# peltier.net
KiCad netlist of a schematic drawn in EAGLE
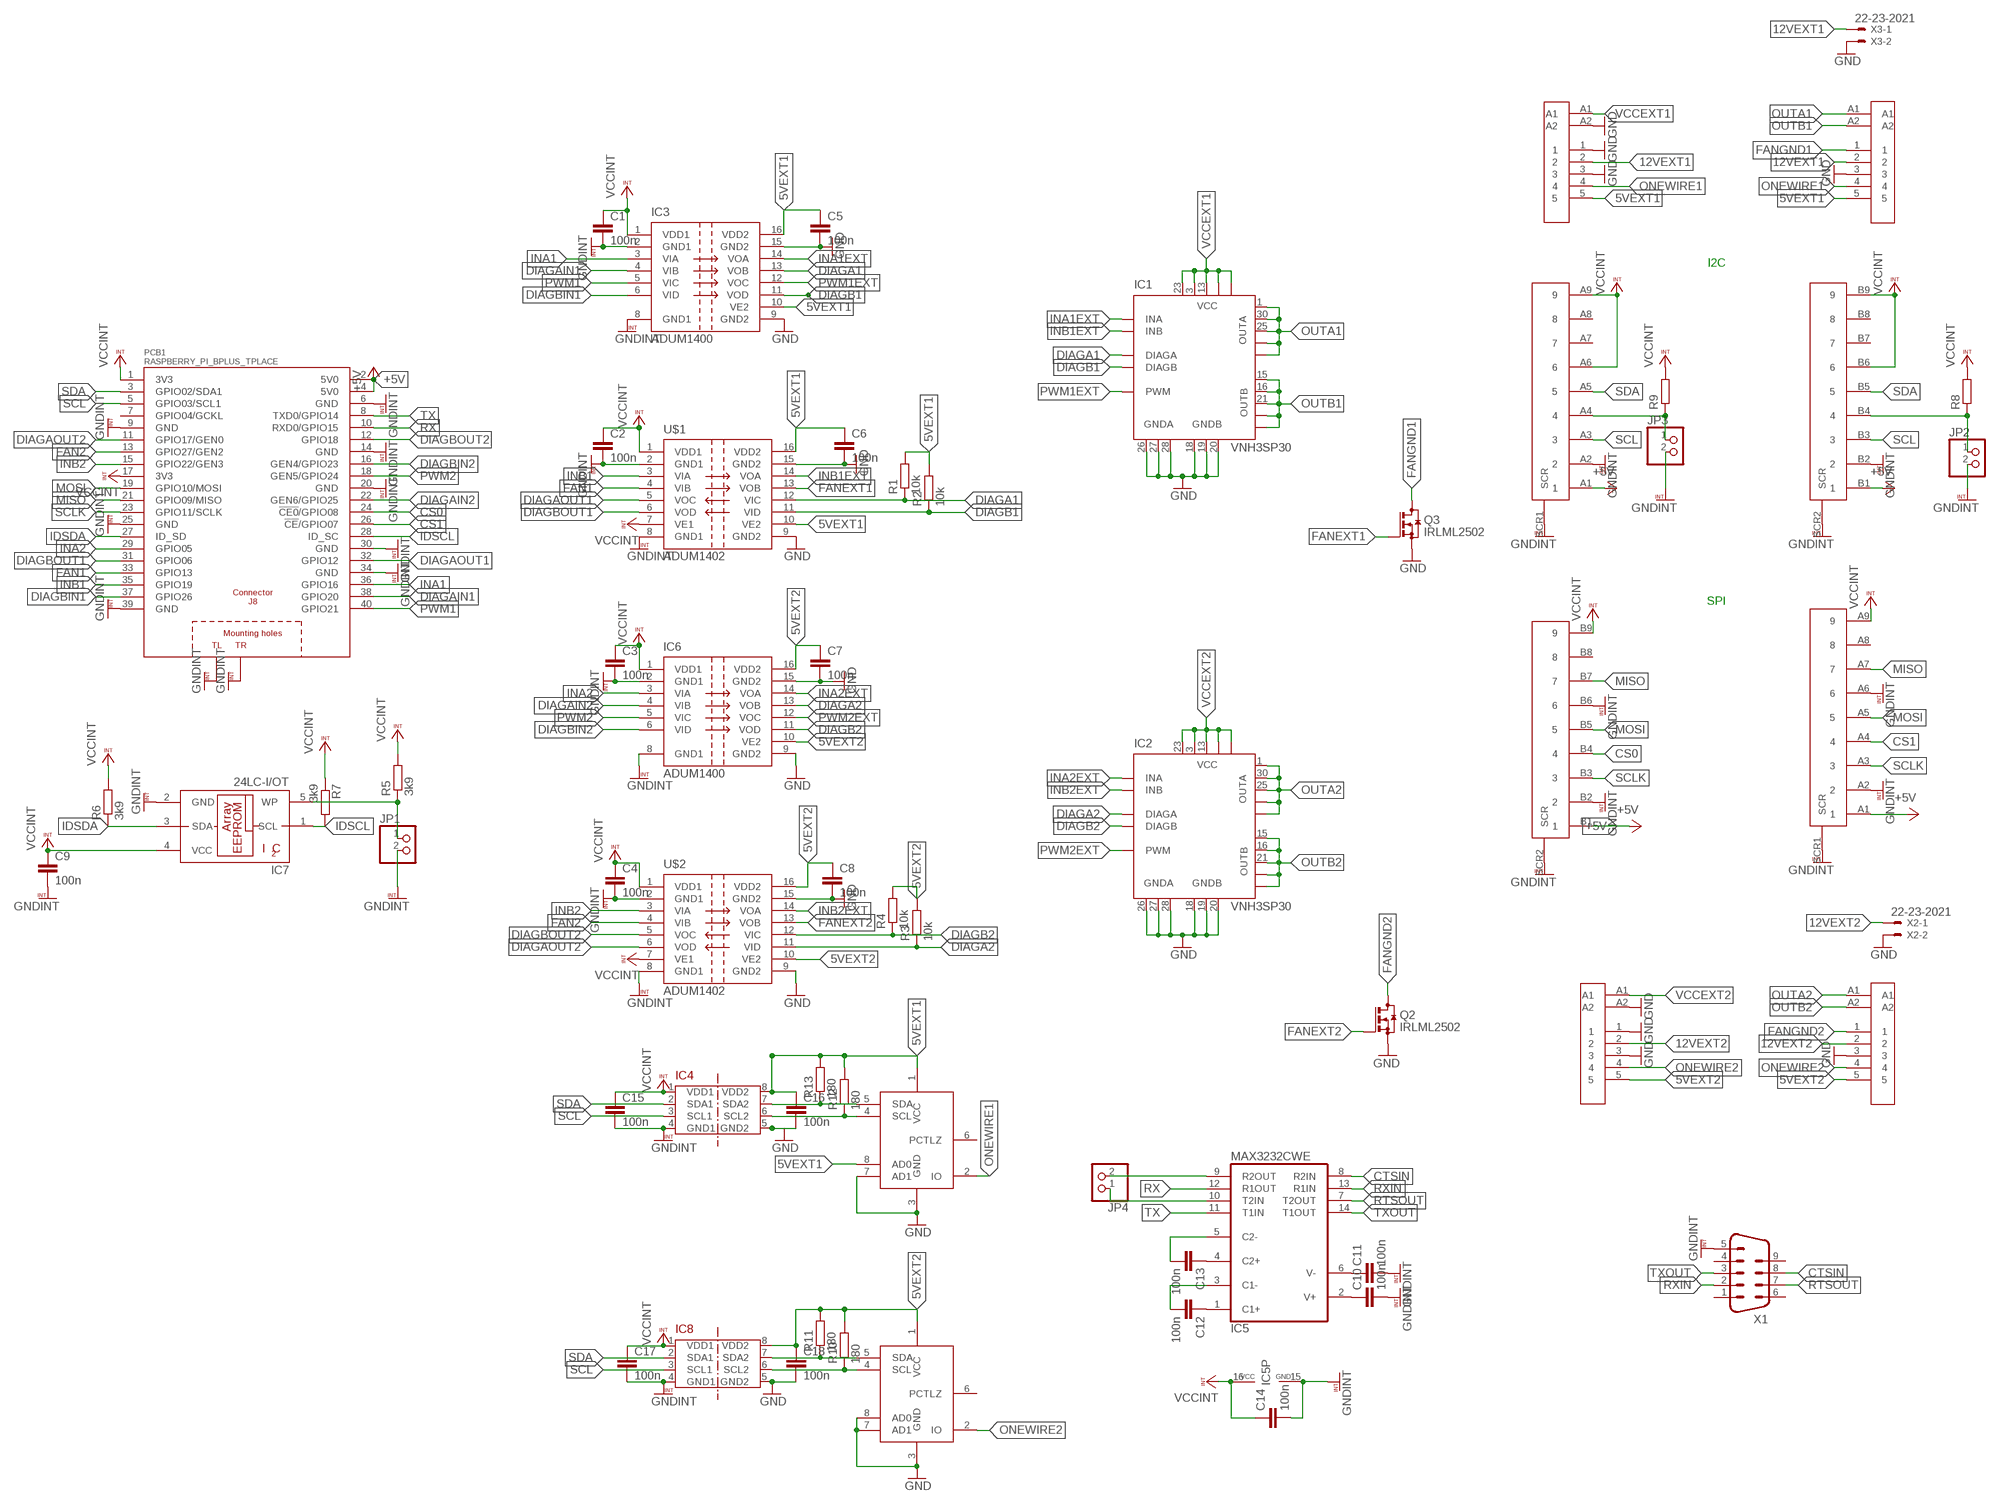
[diagram p0: schematic, sheet 1]

(export (version "E")
  (design (tool "Eeschema 10.0.6"))
  (components
    (comp (ref "C1")
      (value "100n")
      (footprint "eagle-import:C0805")
      (libsource (lib "eagle-import") (part "C-EUC0805"))
    )
    (comp (ref "C2")
      (value "100n")
      (footprint "eagle-import:C0805")
      (libsource (lib "eagle-import") (part "C-EUC0805"))
    )
    (comp (ref "C3")
      (value "100n")
      (footprint "eagle-import:C0805")
      (libsource (lib "eagle-import") (part "C-EUC0805"))
    )
    (comp (ref "C4")
      (value "100n")
      (footprint "eagle-import:C0805")
      (libsource (lib "eagle-import") (part "C-EUC0805"))
    )
    (comp (ref "C5")
      (value "100n")
      (footprint "eagle-import:C0805")
      (libsource (lib "eagle-import") (part "C-EUC0805"))
    )
    (comp (ref "C6")
      (value "100n")
      (footprint "eagle-import:C0805")
      (libsource (lib "eagle-import") (part "C-EUC0805"))
    )
    (comp (ref "C7")
      (value "100n")
      (footprint "eagle-import:C0805")
      (libsource (lib "eagle-import") (part "C-EUC0805"))
    )
    (comp (ref "C8")
      (value "100n")
      (footprint "eagle-import:C0805")
      (libsource (lib "eagle-import") (part "C-EUC0805"))
    )
    (comp (ref "C9")
      (value "100n")
      (footprint "eagle-import:C0805")
      (libsource (lib "eagle-import") (part "C-EUC0805"))
    )
    (comp (ref "C10")
      (value "100n")
      (footprint "eagle-import:C0805")
      (libsource (lib "eagle-import") (part "C-EUC0805"))
    )
    (comp (ref "C11")
      (value "100n")
      (footprint "eagle-import:C0805")
      (libsource (lib "eagle-import") (part "C-EUC0805"))
    )
    (comp (ref "C12")
      (value "100n")
      (footprint "eagle-import:C0805")
      (libsource (lib "eagle-import") (part "C-EUC0805"))
    )
    (comp (ref "C13")
      (value "100n")
      (footprint "eagle-import:C0805")
      (libsource (lib "eagle-import") (part "C-EUC0805"))
    )
    (comp (ref "C14")
      (value "100n")
      (footprint "eagle-import:C0805")
      (libsource (lib "eagle-import") (part "C-EUC0805"))
    )
    (comp (ref "C15")
      (value "100n")
      (footprint "eagle-import:C0805")
      (libsource (lib "eagle-import") (part "C-EUC0805"))
    )
    (comp (ref "C16")
      (value "100n")
      (footprint "eagle-import:C0805")
      (libsource (lib "eagle-import") (part "C-EUC0805"))
    )
    (comp (ref "C17")
      (value "100n")
      (footprint "eagle-import:C0805")
      (libsource (lib "eagle-import") (part "C-EUC0805"))
    )
    (comp (ref "C18")
      (value "100n")
      (footprint "eagle-import:C0805")
      (libsource (lib "eagle-import") (part "C-EUC0805"))
    )
    (comp (ref "IC1")
      (value "VNH3SP30")
      (footprint "eagle-import:MULTIPOWERSO-30")
      (fields (field (name "MPN") "VNH3SP30-E"))
      (libsource (lib "eagle-import") (part "VNH3SP30"))
    )
    (comp (ref "IC2")
      (value "VNH3SP30")
      (footprint "eagle-import:MULTIPOWERSO-30")
      (fields (field (name "MPN") "VNH3SP30-E"))
      (libsource (lib "eagle-import") (part "VNH3SP30"))
    )
    (comp (ref "IC3")
      (value "ADUM1400")
      (footprint "eagle-import:SO16W")
      (libsource (lib "eagle-import") (part "ADUM1400"))
    )
    (comp (ref "IC4")
      (value "ADUM1250")
      (footprint "eagle-import:SO08")
      (libsource (lib "eagle-import") (part "ADUM1250"))
    )
    (comp (ref "IC5")
      (value "MAX3232CWE")
      (footprint "eagle-import:SO16L")
      (fields (field (name "MF") "MAXIM") (field (name "MPN") "MAX3232CWE+"))
      (libsource (lib "eagle-import") (part "MAX3232WEC"))
    )
    (comp (ref "IC6")
      (value "ADUM1400")
      (footprint "eagle-import:SO16W")
      (libsource (lib "eagle-import") (part "ADUM1400"))
    )
    (comp (ref "IC7")
      (value "24LC-I/OT")
      (footprint "eagle-import:SOT23-5")
      (libsource (lib "eagle-import") (part "24LC-I/OT"))
    )
    (comp (ref "IC8")
      (value "ADUM1250")
      (footprint "eagle-import:SO08")
      (libsource (lib "eagle-import") (part "ADUM1250"))
    )
    (comp (ref "JP1")
      (value "PINHD-1X2")
      (footprint "eagle-import:1X02")
      (libsource (lib "eagle-import") (part "PINHD-1X2"))
    )
    (comp (ref "JP2")
      (value "PINHD-1X2")
      (footprint "eagle-import:1X02")
      (libsource (lib "eagle-import") (part "PINHD-1X2"))
    )
    (comp (ref "JP3")
      (value "PINHD-1X2")
      (footprint "eagle-import:1X02")
      (libsource (lib "eagle-import") (part "PINHD-1X2"))
    )
    (comp (ref "JP4")
      (value "PINHD-1X2")
      (footprint "eagle-import:1X02")
      (libsource (lib "eagle-import") (part "PINHD-1X2"))
    )
    (comp (ref "PCB1")
      (value "RASPBERRY_PI_BPLUS_TPLACE")
      (footprint "eagle-import:RASPBERRY_PI_BPLUS_TPLACE")
      (libsource (lib "eagle-import") (part "RASPBERRY_PI_BPLUS_TPLACE"))
    )
    (comp (ref "Q2")
      (value "IRLML2502")
      (footprint "eagle-import:SOT23")
      (libsource (lib "eagle-import") (part "BSS123"))
    )
    (comp (ref "Q3")
      (value "IRLML2502")
      (footprint "eagle-import:SOT23")
      (libsource (lib "eagle-import") (part "BSS123"))
    )
    (comp (ref "R1")
      (value "10k")
      (footprint "eagle-import:R0805")
      (libsource (lib "eagle-import") (part "R-EU_R0805"))
    )
    (comp (ref "R2")
      (value "10k")
      (footprint "eagle-import:R0805")
      (libsource (lib "eagle-import") (part "R-EU_R0805"))
    )
    (comp (ref "R3")
      (value "10k")
      (footprint "eagle-import:R0805")
      (libsource (lib "eagle-import") (part "R-EU_R0805"))
    )
    (comp (ref "R4")
      (value "10k")
      (footprint "eagle-import:R0805")
      (libsource (lib "eagle-import") (part "R-EU_R0805"))
    )
    (comp (ref "R5")
      (value "3k9")
      (footprint "eagle-import:R0805")
      (libsource (lib "eagle-import") (part "R-EU_R0805"))
    )
    (comp (ref "R6")
      (value "3k9")
      (footprint "eagle-import:R0805")
      (libsource (lib "eagle-import") (part "R-EU_R0805"))
    )
    (comp (ref "R7")
      (value "3k9")
      (footprint "eagle-import:R0805")
      (libsource (lib "eagle-import") (part "R-EU_R0805"))
    )
    (comp (ref "R8")
      (value "R-EU_R0805")
      (footprint "eagle-import:R0805")
      (libsource (lib "eagle-import") (part "R-EU_R0805"))
    )
    (comp (ref "R9")
      (value "R-EU_R0805")
      (footprint "eagle-import:R0805")
      (libsource (lib "eagle-import") (part "R-EU_R0805"))
    )
    (comp (ref "R10")
      (value "180")
      (footprint "eagle-import:R0805")
      (libsource (lib "eagle-import") (part "R-EU_R0805"))
    )
    (comp (ref "R11")
      (value "180")
      (footprint "eagle-import:R0805")
      (libsource (lib "eagle-import") (part "R-EU_R0805"))
    )
    (comp (ref "R12")
      (value "180")
      (footprint "eagle-import:R0805")
      (libsource (lib "eagle-import") (part "R-EU_R0805"))
    )
    (comp (ref "R13")
      (value "180")
      (footprint "eagle-import:R0805")
      (libsource (lib "eagle-import") (part "R-EU_R0805"))
    )
    (comp (ref "U$1")
      (value "ADUM1402")
      (footprint "eagle-import:SO16W")
      (libsource (lib "eagle-import") (part "ADUM1402"))
    )
    (comp (ref "U$2")
      (value "ADUM1402")
      (footprint "eagle-import:SO16W")
      (libsource (lib "eagle-import") (part "ADUM1402"))
    )
    (comp (ref "U$3")
      (value "7W2-F")
      (footprint "eagle-import:7W2-F")
      (libsource (lib "eagle-import") (part "7W2-F"))
    )
    (comp (ref "U$4")
      (value "7W2-F")
      (footprint "eagle-import:7W2-F")
      (libsource (lib "eagle-import") (part "7W2-F"))
    )
    (comp (ref "U$5")
      (value "7W2-M")
      (footprint "eagle-import:7W2-M")
      (libsource (lib "eagle-import") (part "7W2-M"))
    )
    (comp (ref "U$6")
      (value "7W2-M")
      (footprint "eagle-import:7W2-M")
      (libsource (lib "eagle-import") (part "7W2-M"))
    )
    (comp (ref "U$11")
      (value "164A19919X")
      (footprint "eagle-import:164A19919X")
      (libsource (lib "eagle-import") (part "164A19919X"))
    )
    (comp (ref "U$12")
      (value "164A19919X")
      (footprint "eagle-import:164A19919X")
      (libsource (lib "eagle-import") (part "164A19919X"))
    )
    (comp (ref "U$14")
      (value "DS2483-100")
      (footprint "eagle-import:SO-08")
      (libsource (lib "eagle-import") (part "DS2483-100"))
    )
    (comp (ref "U$15")
      (value "DS2483-100")
      (footprint "eagle-import:SO-08")
      (libsource (lib "eagle-import") (part "DS2483-100"))
    )
    (comp (ref "X1")
      (value "M09HP")
      (footprint "eagle-import:M09HP")
      (libsource (lib "eagle-import") (part "M09HP"))
    )
    (comp (ref "X2")
      (value "22-23-2021")
      (footprint "eagle-import:22-23-2021")
      (fields (field (name "MF") "MOLEX"))
      (libsource (lib "eagle-import") (part "22-23-2021"))
    )
    (comp (ref "X3")
      (value "22-23-2021")
      (footprint "eagle-import:22-23-2021")
      (fields (field (name "MF") "MOLEX"))
      (libsource (lib "eagle-import") (part "22-23-2021"))
    )
  )
  (nets
    (net (code "1") (name "+5V") (class "Default")
      (node (ref "PCB1") (pin "2") (pinfunction "5V0_2") (pintype "power_in"))
      (node (ref "PCB1") (pin "4") (pinfunction "5V0_4") (pintype "power_in"))
      (node (ref "U$11") (pin "A1") (pinfunction "1_A1") (pintype "bidirectional"))
      (node (ref "U$11") (pin "B1") (pinfunction "1_B1") (pintype "bidirectional"))
      (node (ref "U$12") (pin "A1") (pinfunction "1_A1") (pintype "bidirectional"))
      (node (ref "U$12") (pin "B1") (pinfunction "1_B1") (pintype "bidirectional"))
    )
    (net (code "2") (name "5VEXT1") (class "Default")
      (node (ref "C16") (pin "1") (pinfunction "1_1") (pintype "passive"))
      (node (ref "C5") (pin "1") (pinfunction "1_1") (pintype "passive"))
      (node (ref "C6") (pin "1") (pinfunction "1_1") (pintype "passive"))
      (node (ref "IC3") (pin "10") (pinfunction "VE2_10") (pintype "passive"))
      (node (ref "IC3") (pin "16") (pinfunction "VDD2_16") (pintype "power_in"))
      (node (ref "IC4") (pin "8") (pinfunction "VDD2_8") (pintype "power_in"))
      (node (ref "R1") (pin "2") (pinfunction "2_2") (pintype "passive"))
      (node (ref "R12") (pin "2") (pinfunction "2_2") (pintype "passive"))
      (node (ref "R13") (pin "2") (pinfunction "2_2") (pintype "passive"))
      (node (ref "R2") (pin "2") (pinfunction "2_2") (pintype "passive"))
      (node (ref "U$1") (pin "10") (pinfunction "VE2_10") (pintype "passive"))
      (node (ref "U$1") (pin "16") (pinfunction "VDD2_16") (pintype "power_in"))
      (node (ref "U$14") (pin "1") (pinfunction "VCC_1") (pintype "bidirectional"))
      (node (ref "U$14") (pin "8") (pinfunction "AD0_8") (pintype "bidirectional"))
      (node (ref "U$3") (pin "5") (pinfunction "5_5") (pintype "bidirectional"))
      (node (ref "U$5") (pin "5") (pinfunction "5_5") (pintype "bidirectional"))
    )
    (net (code "3") (name "5VEXT2") (class "Default")
      (node (ref "C18") (pin "1") (pinfunction "1_1") (pintype "passive"))
      (node (ref "C7") (pin "1") (pinfunction "1_1") (pintype "passive"))
      (node (ref "C8") (pin "1") (pinfunction "1_1") (pintype "passive"))
      (node (ref "IC6") (pin "10") (pinfunction "VE2_10") (pintype "passive"))
      (node (ref "IC6") (pin "16") (pinfunction "VDD2_16") (pintype "power_in"))
      (node (ref "IC8") (pin "8") (pinfunction "VDD2_8") (pintype "power_in"))
      (node (ref "R10") (pin "2") (pinfunction "2_2") (pintype "passive"))
      (node (ref "R11") (pin "2") (pinfunction "2_2") (pintype "passive"))
      (node (ref "R3") (pin "2") (pinfunction "2_2") (pintype "passive"))
      (node (ref "R4") (pin "2") (pinfunction "2_2") (pintype "passive"))
      (node (ref "U$15") (pin "1") (pinfunction "VCC_1") (pintype "bidirectional"))
      (node (ref "U$2") (pin "10") (pinfunction "VE2_10") (pintype "passive"))
      (node (ref "U$2") (pin "16") (pinfunction "VDD2_16") (pintype "power_in"))
      (node (ref "U$4") (pin "5") (pinfunction "5_5") (pintype "bidirectional"))
      (node (ref "U$6") (pin "5") (pinfunction "5_5") (pintype "bidirectional"))
    )
    (net (code "4") (name "12VEXT1") (class "Default")
      (node (ref "U$3") (pin "2") (pinfunction "2_2") (pintype "bidirectional"))
      (node (ref "U$5") (pin "2") (pinfunction "2_2") (pintype "bidirectional"))
      (node (ref "X3") (pin "1") (pinfunction "S_1") (pintype "passive"))
    )
    (net (code "5") (name "12VEXT2") (class "Default")
      (node (ref "U$4") (pin "2") (pinfunction "2_2") (pintype "bidirectional"))
      (node (ref "U$6") (pin "2") (pinfunction "2_2") (pintype "bidirectional"))
      (node (ref "X2") (pin "1") (pinfunction "S_1") (pintype "passive"))
    )
    (net (code "6") (name "CS0") (class "Default")
      (node (ref "PCB1") (pin "24") (pinfunction "~{CE0}/GPIO08_24") (pintype "bidirectional"))
      (node (ref "U$12") (pin "B4") (pinfunction "4_B4") (pintype "bidirectional"))
    )
    (net (code "7") (name "CS1") (class "Default")
      (node (ref "PCB1") (pin "26") (pinfunction "~{CE}/GPIO07_26") (pintype "bidirectional"))
      (node (ref "U$12") (pin "A4") (pinfunction "4_A4") (pintype "bidirectional"))
    )
    (net (code "8") (name "CTSIN") (class "Default")
      (node (ref "IC5") (pin "8") (pinfunction "R2IN_8") (pintype "input"))
      (node (ref "X1") (pin "8") (pinfunction "8_8") (pintype "passive"))
    )
    (net (code "9") (name "DIAGA1") (class "Default")
      (node (ref "IC1") (pin "6") (pinfunction "DIAGA_6") (pintype "open_collector"))
      (node (ref "IC3") (pin "13") (pinfunction "VOB_13") (pintype "output"))
      (node (ref "R1") (pin "1") (pinfunction "1_1") (pintype "passive"))
      (node (ref "U$1") (pin "12") (pinfunction "VIC_12") (pintype "input"))
    )
    (net (code "10") (name "DIAGA2") (class "Default")
      (node (ref "IC2") (pin "6") (pinfunction "DIAGA_6") (pintype "open_collector"))
      (node (ref "IC6") (pin "13") (pinfunction "VOB_13") (pintype "output"))
      (node (ref "R3") (pin "1") (pinfunction "1_1") (pintype "passive"))
      (node (ref "U$2") (pin "11") (pinfunction "VID_11") (pintype "input"))
    )
    (net (code "11") (name "DIAGAIN1") (class "Default")
      (node (ref "IC3") (pin "4") (pinfunction "VIB_4") (pintype "input"))
      (node (ref "PCB1") (pin "38") (pinfunction "GPIO20_38") (pintype "bidirectional"))
    )
    (net (code "12") (name "DIAGAIN2") (class "Default")
      (node (ref "IC6") (pin "4") (pinfunction "VIB_4") (pintype "input"))
      (node (ref "PCB1") (pin "22") (pinfunction "GEN6/GPIO25_22") (pintype "bidirectional"))
    )
    (net (code "13") (name "DIAGAOUT1") (class "Default")
      (node (ref "PCB1") (pin "32") (pinfunction "GPIO12_32") (pintype "bidirectional"))
      (node (ref "U$1") (pin "5") (pinfunction "VOC_5") (pintype "output"))
    )
    (net (code "14") (name "DIAGAOUT2") (class "Default")
      (node (ref "PCB1") (pin "11") (pinfunction "GPIO17/GEN0_11") (pintype "bidirectional"))
      (node (ref "U$2") (pin "6") (pinfunction "VOD_6") (pintype "output"))
    )
    (net (code "15") (name "DIAGB1") (class "Default")
      (node (ref "IC1") (pin "10") (pinfunction "DIAGB_10") (pintype "open_collector"))
      (node (ref "IC3") (pin "11") (pinfunction "VOD_11") (pintype "output"))
      (node (ref "R2") (pin "1") (pinfunction "1_1") (pintype "passive"))
      (node (ref "U$1") (pin "11") (pinfunction "VID_11") (pintype "input"))
    )
    (net (code "16") (name "DIAGB2") (class "Default")
      (node (ref "IC2") (pin "10") (pinfunction "DIAGB_10") (pintype "open_collector"))
      (node (ref "IC6") (pin "11") (pinfunction "VOD_11") (pintype "output"))
      (node (ref "R4") (pin "1") (pinfunction "1_1") (pintype "passive"))
      (node (ref "U$2") (pin "12") (pinfunction "VIC_12") (pintype "input"))
    )
    (net (code "17") (name "DIAGBIN1") (class "Default")
      (node (ref "IC3") (pin "6") (pinfunction "VID_6") (pintype "input"))
      (node (ref "PCB1") (pin "37") (pinfunction "GPIO26_37") (pintype "bidirectional"))
    )
    (net (code "18") (name "DIAGBIN2") (class "Default")
      (node (ref "IC6") (pin "6") (pinfunction "VID_6") (pintype "input"))
      (node (ref "PCB1") (pin "16") (pinfunction "GEN4/GPIO23_16") (pintype "bidirectional"))
    )
    (net (code "19") (name "DIAGBOUT1") (class "Default")
      (node (ref "PCB1") (pin "31") (pinfunction "GPIO06_31") (pintype "bidirectional"))
      (node (ref "U$1") (pin "6") (pinfunction "VOD_6") (pintype "output"))
    )
    (net (code "20") (name "DIAGBOUT2") (class "Default")
      (node (ref "PCB1") (pin "12") (pinfunction "GPIO18_12") (pintype "bidirectional"))
      (node (ref "U$2") (pin "5") (pinfunction "VOC_5") (pintype "output"))
    )
    (net (code "21") (name "FAN1") (class "Default")
      (node (ref "PCB1") (pin "33") (pinfunction "GPIO13_33") (pintype "bidirectional"))
      (node (ref "U$1") (pin "4") (pinfunction "VIB_4") (pintype "input"))
    )
    (net (code "22") (name "FAN2") (class "Default")
      (node (ref "PCB1") (pin "13") (pinfunction "GPIO27/GEN2_13") (pintype "bidirectional"))
      (node (ref "U$2") (pin "4") (pinfunction "VIB_4") (pintype "input"))
    )
    (net (code "23") (name "FANEXT1") (class "Default")
      (node (ref "Q3") (pin "1") (pinfunction "G_1") (pintype "passive"))
      (node (ref "U$1") (pin "13") (pinfunction "VOB_13") (pintype "output"))
    )
    (net (code "24") (name "FANEXT2") (class "Default")
      (node (ref "Q2") (pin "1") (pinfunction "G_1") (pintype "passive"))
      (node (ref "U$2") (pin "13") (pinfunction "VOB_13") (pintype "output"))
    )
    (net (code "25") (name "FANGND1") (class "Default")
      (node (ref "Q3") (pin "3") (pinfunction "D_3") (pintype "passive"))
      (node (ref "U$3") (pin "1") (pinfunction "1_1") (pintype "bidirectional"))
    )
    (net (code "26") (name "FANGND2") (class "Default")
      (node (ref "Q2") (pin "3") (pinfunction "D_3") (pintype "passive"))
      (node (ref "U$4") (pin "1") (pinfunction "1_1") (pintype "bidirectional"))
    )
    (net (code "27") (name "GND") (class "Default")
      (node (ref "C16") (pin "2") (pinfunction "2_2") (pintype "passive"))
      (node (ref "C18") (pin "2") (pinfunction "2_2") (pintype "passive"))
      (node (ref "C5") (pin "2") (pinfunction "2_2") (pintype "passive"))
      (node (ref "C6") (pin "2") (pinfunction "2_2") (pintype "passive"))
      (node (ref "C7") (pin "2") (pinfunction "2_2") (pintype "passive"))
      (node (ref "C8") (pin "2") (pinfunction "2_2") (pintype "passive"))
      (node (ref "IC1") (pin "18") (pinfunction "GNDB_18") (pintype "power_in"))
      (node (ref "IC1") (pin "19") (pinfunction "GNDB_19") (pintype "power_in"))
      (node (ref "IC1") (pin "20") (pinfunction "GNDB_20") (pintype "power_in"))
      (node (ref "IC1") (pin "26") (pinfunction "GNDA_26") (pintype "power_in"))
      (node (ref "IC1") (pin "27") (pinfunction "GNDA_27") (pintype "power_in"))
      (node (ref "IC1") (pin "28") (pinfunction "GNDA_28") (pintype "power_in"))
      (node (ref "IC2") (pin "18") (pinfunction "GNDB_18") (pintype "power_in"))
      (node (ref "IC2") (pin "19") (pinfunction "GNDB_19") (pintype "power_in"))
      (node (ref "IC2") (pin "20") (pinfunction "GNDB_20") (pintype "power_in"))
      (node (ref "IC2") (pin "26") (pinfunction "GNDA_26") (pintype "power_in"))
      (node (ref "IC2") (pin "27") (pinfunction "GNDA_27") (pintype "power_in"))
      (node (ref "IC2") (pin "28") (pinfunction "GNDA_28") (pintype "power_in"))
      (node (ref "IC3") (pin "15") (pinfunction "GND2_15") (pintype "power_in"))
      (node (ref "IC3") (pin "9") (pinfunction "GND2_9") (pintype "power_in"))
      (node (ref "IC4") (pin "5") (pinfunction "GND2_5") (pintype "power_in"))
      (node (ref "IC6") (pin "15") (pinfunction "GND2_15") (pintype "power_in"))
      (node (ref "IC6") (pin "9") (pinfunction "GND2_9") (pintype "power_in"))
      (node (ref "IC8") (pin "5") (pinfunction "GND2_5") (pintype "power_in"))
      (node (ref "Q2") (pin "2") (pinfunction "S_2") (pintype "passive"))
      (node (ref "Q3") (pin "2") (pinfunction "S_2") (pintype "passive"))
      (node (ref "U$1") (pin "15") (pinfunction "GND2_15") (pintype "power_in"))
      (node (ref "U$1") (pin "9") (pinfunction "GND2_9") (pintype "power_in"))
      (node (ref "U$14") (pin "3") (pinfunction "GND_3") (pintype "bidirectional"))
      (node (ref "U$14") (pin "7") (pinfunction "AD1_7") (pintype "bidirectional"))
      (node (ref "U$15") (pin "3") (pinfunction "GND_3") (pintype "bidirectional"))
      (node (ref "U$15") (pin "7") (pinfunction "AD1_7") (pintype "bidirectional"))
      (node (ref "U$15") (pin "8") (pinfunction "AD0_8") (pintype "bidirectional"))
      (node (ref "U$2") (pin "15") (pinfunction "GND2_15") (pintype "power_in"))
      (node (ref "U$2") (pin "9") (pinfunction "GND2_9") (pintype "power_in"))
      (node (ref "U$3") (pin "3") (pinfunction "3_3") (pintype "bidirectional"))
      (node (ref "U$4") (pin "3") (pinfunction "3_3") (pintype "bidirectional"))
      (node (ref "U$5") (pin "1") (pinfunction "1_1") (pintype "bidirectional"))
      (node (ref "U$5") (pin "3") (pinfunction "3_3") (pintype "bidirectional"))
      (node (ref "U$5") (pin "A2") (pinfunction "A2_A2") (pintype "bidirectional"))
      (node (ref "U$6") (pin "1") (pinfunction "1_1") (pintype "bidirectional"))
      (node (ref "U$6") (pin "3") (pinfunction "3_3") (pintype "bidirectional"))
      (node (ref "U$6") (pin "A2") (pinfunction "A2_A2") (pintype "bidirectional"))
      (node (ref "X2") (pin "2") (pinfunction "S_2") (pintype "passive"))
      (node (ref "X3") (pin "2") (pinfunction "S_2") (pintype "passive"))
    )
    (net (code "28") (name "GNDINT") (class "Default")
      (node (ref "C1") (pin "2") (pinfunction "2_2") (pintype "passive"))
      (node (ref "C10") (pin "2") (pinfunction "2_2") (pintype "passive"))
      (node (ref "C11") (pin "2") (pinfunction "2_2") (pintype "passive"))
      (node (ref "C14") (pin "2") (pinfunction "2_2") (pintype "passive"))
      (node (ref "C15") (pin "2") (pinfunction "2_2") (pintype "passive"))
      (node (ref "C17") (pin "2") (pinfunction "2_2") (pintype "passive"))
      (node (ref "C2") (pin "2") (pinfunction "2_2") (pintype "passive"))
      (node (ref "C3") (pin "2") (pinfunction "2_2") (pintype "passive"))
      (node (ref "C4") (pin "2") (pinfunction "2_2") (pintype "passive"))
      (node (ref "C9") (pin "2") (pinfunction "2_2") (pintype "passive"))
      (node (ref "IC3") (pin "2") (pinfunction "GND1_2") (pintype "power_in"))
      (node (ref "IC3") (pin "8") (pinfunction "GND1_8") (pintype "power_in"))
      (node (ref "IC4") (pin "4") (pinfunction "GND1_4") (pintype "power_in"))
      (node (ref "IC5") (pin "15") (pinfunction "GND_15") (pintype "power_in"))
      (node (ref "IC6") (pin "2") (pinfunction "GND1_2") (pintype "power_in"))
      (node (ref "IC6") (pin "8") (pinfunction "GND1_8") (pintype "power_in"))
      (node (ref "IC7") (pin "2") (pinfunction "GND_2") (pintype "power_in"))
      (node (ref "IC8") (pin "4") (pinfunction "GND1_4") (pintype "power_in"))
      (node (ref "JP1") (pin "2") (pinfunction "2_2") (pintype "passive"))
      (node (ref "JP2") (pin "2") (pinfunction "2_2") (pintype "passive"))
      (node (ref "JP3") (pin "2") (pinfunction "2_2") (pintype "passive"))
      (node (ref "PCB1") (pin "14") (pinfunction "GND_14") (pintype "power_in"))
      (node (ref "PCB1") (pin "20") (pinfunction "GND_20") (pintype "power_in"))
      (node (ref "PCB1") (pin "25") (pinfunction "GND_25") (pintype "power_in"))
      (node (ref "PCB1") (pin "30") (pinfunction "GND_30") (pintype "power_in"))
      (node (ref "PCB1") (pin "34") (pinfunction "GND_34") (pintype "power_in"))
      (node (ref "PCB1") (pin "39") (pinfunction "GND_39") (pintype "power_in"))
      (node (ref "PCB1") (pin "6") (pinfunction "GND_6") (pintype "power_in"))
      (node (ref "PCB1") (pin "9") (pinfunction "GND_9") (pintype "power_in"))
      (node (ref "PCB1") (pin "PE_TL") (pinfunction "TL_PE_TL") (pintype "bidirectional"))
      (node (ref "PCB1") (pin "PE_TR") (pinfunction "TR_PE_TR") (pintype "bidirectional"))
      (node (ref "U$1") (pin "2") (pinfunction "GND1_2") (pintype "power_in"))
      (node (ref "U$1") (pin "8") (pinfunction "GND1_8") (pintype "power_in"))
      (node (ref "U$11") (pin "A2") (pinfunction "2_A2") (pintype "bidirectional"))
      (node (ref "U$11") (pin "B2") (pinfunction "2_B2") (pintype "bidirectional"))
      (node (ref "U$11") (pin "SCR1") (pinfunction "SCR_SCR1") (pintype "bidirectional"))
      (node (ref "U$11") (pin "SCR2") (pinfunction "SCR_SCR2") (pintype "bidirectional"))
      (node (ref "U$12") (pin "A2") (pinfunction "2_A2") (pintype "bidirectional"))
      (node (ref "U$12") (pin "A6") (pinfunction "6_A6") (pintype "bidirectional"))
      (node (ref "U$12") (pin "B2") (pinfunction "2_B2") (pintype "bidirectional"))
      (node (ref "U$12") (pin "B6") (pinfunction "6_B6") (pintype "bidirectional"))
      (node (ref "U$12") (pin "SCR1") (pinfunction "SCR_SCR1") (pintype "bidirectional"))
      (node (ref "U$12") (pin "SCR2") (pinfunction "SCR_SCR2") (pintype "bidirectional"))
      (node (ref "U$2") (pin "2") (pinfunction "GND1_2") (pintype "power_in"))
      (node (ref "U$2") (pin "8") (pinfunction "GND1_8") (pintype "power_in"))
      (node (ref "X1") (pin "5") (pinfunction "5_5") (pintype "passive"))
    )
    (net (code "29") (name "IDSCL") (class "Default")
      (node (ref "IC7") (pin "1") (pinfunction "SCL_1") (pintype "bidirectional"))
      (node (ref "PCB1") (pin "28") (pinfunction "ID_SC_28") (pintype "bidirectional"))
      (node (ref "R7") (pin "2") (pinfunction "2_2") (pintype "passive"))
    )
    (net (code "30") (name "IDSDA") (class "Default")
      (node (ref "IC7") (pin "3") (pinfunction "SDA_3") (pintype "bidirectional"))
      (node (ref "PCB1") (pin "27") (pinfunction "ID_SD_27") (pintype "bidirectional"))
      (node (ref "R6") (pin "1") (pinfunction "1_1") (pintype "passive"))
    )
    (net (code "31") (name "INA1") (class "Default")
      (node (ref "IC3") (pin "3") (pinfunction "VIA_3") (pintype "input"))
      (node (ref "PCB1") (pin "36") (pinfunction "GPIO16_36") (pintype "bidirectional"))
    )
    (net (code "32") (name "INA1EXT") (class "Default")
      (node (ref "IC1") (pin "5") (pinfunction "INA_5") (pintype "input"))
      (node (ref "IC3") (pin "14") (pinfunction "VOA_14") (pintype "output"))
    )
    (net (code "33") (name "INA2") (class "Default")
      (node (ref "IC6") (pin "3") (pinfunction "VIA_3") (pintype "input"))
      (node (ref "PCB1") (pin "29") (pinfunction "GPIO05_29") (pintype "bidirectional"))
    )
    (net (code "34") (name "INA2EXT") (class "Default")
      (node (ref "IC2") (pin "5") (pinfunction "INA_5") (pintype "input"))
      (node (ref "IC6") (pin "14") (pinfunction "VOA_14") (pintype "output"))
    )
    (net (code "35") (name "INB1") (class "Default")
      (node (ref "PCB1") (pin "35") (pinfunction "GPIO19_35") (pintype "bidirectional"))
      (node (ref "U$1") (pin "3") (pinfunction "VIA_3") (pintype "input"))
    )
    (net (code "36") (name "INB1EXT") (class "Default")
      (node (ref "IC1") (pin "11") (pinfunction "INB_11") (pintype "input"))
      (node (ref "U$1") (pin "14") (pinfunction "VOA_14") (pintype "output"))
    )
    (net (code "37") (name "INB2") (class "Default")
      (node (ref "PCB1") (pin "15") (pinfunction "GPIO22/GEN3_15") (pintype "bidirectional"))
      (node (ref "U$2") (pin "3") (pinfunction "VIA_3") (pintype "input"))
    )
    (net (code "38") (name "INB2EXT") (class "Default")
      (node (ref "IC2") (pin "11") (pinfunction "INB_11") (pintype "input"))
      (node (ref "U$2") (pin "14") (pinfunction "VOA_14") (pintype "output"))
    )
    (net (code "39") (name "MISO") (class "Default")
      (node (ref "PCB1") (pin "21") (pinfunction "GPIO09/MISO_21") (pintype "bidirectional"))
      (node (ref "U$12") (pin "A7") (pinfunction "7_A7") (pintype "bidirectional"))
      (node (ref "U$12") (pin "B7") (pinfunction "7_B7") (pintype "bidirectional"))
    )
    (net (code "40") (name "MOSI") (class "Default")
      (node (ref "PCB1") (pin "19") (pinfunction "GPIO10/MOSI_19") (pintype "bidirectional"))
      (node (ref "U$12") (pin "A5") (pinfunction "5_A5") (pintype "bidirectional"))
      (node (ref "U$12") (pin "B5") (pinfunction "5_B5") (pintype "bidirectional"))
    )
    (net (code "41") (name "Net-(IC4-SCL2)") (class "Default")
      (node (ref "IC4") (pin "6") (pinfunction "SCL2_6") (pintype "bidirectional"))
      (node (ref "R12") (pin "1") (pinfunction "1_1") (pintype "passive"))
      (node (ref "U$14") (pin "4") (pinfunction "SCL_4") (pintype "bidirectional"))
    )
    (net (code "42") (name "Net-(IC4-SDA2)") (class "Default")
      (node (ref "IC4") (pin "7") (pinfunction "SDA2_7") (pintype "bidirectional"))
      (node (ref "R13") (pin "1") (pinfunction "1_1") (pintype "passive"))
      (node (ref "U$14") (pin "5") (pinfunction "SDA_5") (pintype "bidirectional"))
    )
    (net (code "43") (name "Net-(IC5A-C1+)") (class "Default")
      (node (ref "C12") (pin "1") (pinfunction "1_1") (pintype "passive"))
      (node (ref "IC5") (pin "1") (pinfunction "C1+_1") (pintype "bidirectional"))
    )
    (net (code "44") (name "Net-(IC5A-C1-)") (class "Default")
      (node (ref "C12") (pin "2") (pinfunction "2_2") (pintype "passive"))
      (node (ref "IC5") (pin "3") (pinfunction "C1-_3") (pintype "bidirectional"))
    )
    (net (code "45") (name "Net-(IC5A-C2+)") (class "Default")
      (node (ref "C13") (pin "1") (pinfunction "1_1") (pintype "passive"))
      (node (ref "IC5") (pin "4") (pinfunction "C2+_4") (pintype "bidirectional"))
    )
    (net (code "46") (name "Net-(IC5A-C2-)") (class "Default")
      (node (ref "C13") (pin "2") (pinfunction "2_2") (pintype "passive"))
      (node (ref "IC5") (pin "5") (pinfunction "C2-_5") (pintype "bidirectional"))
    )
    (net (code "47") (name "Net-(IC5A-R2OUT)") (class "Default")
      (node (ref "IC5") (pin "9") (pinfunction "R2OUT_9") (pintype "output"))
      (node (ref "JP4") (pin "2") (pinfunction "2_2") (pintype "passive"))
    )
    (net (code "48") (name "Net-(IC5A-T2IN)") (class "Default")
      (node (ref "IC5") (pin "10") (pinfunction "T2IN_10") (pintype "input"))
      (node (ref "JP4") (pin "1") (pinfunction "1_1") (pintype "passive"))
    )
    (net (code "49") (name "Net-(IC5A-V+)") (class "Default")
      (node (ref "C10") (pin "1") (pinfunction "1_1") (pintype "passive"))
      (node (ref "IC5") (pin "2") (pinfunction "V+_2") (pintype "bidirectional"))
    )
    (net (code "50") (name "Net-(IC5A-V-)") (class "Default")
      (node (ref "C11") (pin "1") (pinfunction "1_1") (pintype "passive"))
      (node (ref "IC5") (pin "6") (pinfunction "V-_6") (pintype "bidirectional"))
    )
    (net (code "51") (name "Net-(IC7-WP)") (class "Default")
      (node (ref "IC7") (pin "5") (pinfunction "WP_5") (pintype "bidirectional"))
      (node (ref "JP1") (pin "1") (pinfunction "1_1") (pintype "passive"))
      (node (ref "R5") (pin "1") (pinfunction "1_1") (pintype "passive"))
    )
    (net (code "52") (name "Net-(IC8-SCL2)") (class "Default")
      (node (ref "IC8") (pin "6") (pinfunction "SCL2_6") (pintype "bidirectional"))
      (node (ref "R10") (pin "1") (pinfunction "1_1") (pintype "passive"))
      (node (ref "U$15") (pin "4") (pinfunction "SCL_4") (pintype "bidirectional"))
    )
    (net (code "53") (name "Net-(IC8-SDA2)") (class "Default")
      (node (ref "IC8") (pin "7") (pinfunction "SDA2_7") (pintype "bidirectional"))
      (node (ref "R11") (pin "1") (pinfunction "1_1") (pintype "passive"))
      (node (ref "U$15") (pin "5") (pinfunction "SDA_5") (pintype "bidirectional"))
    )
    (net (code "54") (name "Net-(U$11A-4)") (class "Default")
      (node (ref "JP3") (pin "1") (pinfunction "1_1") (pintype "passive"))
      (node (ref "R9") (pin "1") (pinfunction "1_1") (pintype "passive"))
      (node (ref "U$11") (pin "A4") (pinfunction "4_A4") (pintype "bidirectional"))
    )
    (net (code "55") (name "Net-(U$11B-4)") (class "Default")
      (node (ref "JP2") (pin "1") (pinfunction "1_1") (pintype "passive"))
      (node (ref "R8") (pin "1") (pinfunction "1_1") (pintype "passive"))
      (node (ref "U$11") (pin "B4") (pinfunction "4_B4") (pintype "bidirectional"))
    )
    (net (code "56") (name "ONEWIRE1") (class "Default")
      (node (ref "U$14") (pin "2") (pinfunction "IO_2") (pintype "bidirectional"))
      (node (ref "U$3") (pin "4") (pinfunction "4_4") (pintype "bidirectional"))
      (node (ref "U$5") (pin "4") (pinfunction "4_4") (pintype "bidirectional"))
    )
    (net (code "57") (name "ONEWIRE2") (class "Default")
      (node (ref "U$15") (pin "2") (pinfunction "IO_2") (pintype "bidirectional"))
      (node (ref "U$4") (pin "4") (pinfunction "4_4") (pintype "bidirectional"))
      (node (ref "U$6") (pin "4") (pinfunction "4_4") (pintype "bidirectional"))
    )
    (net (code "58") (name "OUTA1") (class "Default")
      (node (ref "IC1") (pin "1") (pinfunction "OUTA_1") (pintype "output"))
      (node (ref "IC1") (pin "25") (pinfunction "OUTA_25") (pintype "passive"))
      (node (ref "IC1") (pin "30") (pinfunction "OUTA_30") (pintype "passive"))
      (node (ref "IC1") (pin "OUTA") (pinfunction "OUTA_OUTA") (pintype "passive"))
      (node (ref "IC1") (pin "OUTA@1") (pinfunction "OUTA_OUTA@1") (pintype "passive"))
      (node (ref "U$3") (pin "A1") (pinfunction "A1_A1") (pintype "bidirectional"))
    )
    (net (code "59") (name "OUTA2") (class "Default")
      (node (ref "IC2") (pin "1") (pinfunction "OUTA_1") (pintype "output"))
      (node (ref "IC2") (pin "25") (pinfunction "OUTA_25") (pintype "passive"))
      (node (ref "IC2") (pin "30") (pinfunction "OUTA_30") (pintype "passive"))
      (node (ref "IC2") (pin "OUTA") (pinfunction "OUTA_OUTA") (pintype "passive"))
      (node (ref "IC2") (pin "OUTA@1") (pinfunction "OUTA_OUTA@1") (pintype "passive"))
      (node (ref "U$4") (pin "A1") (pinfunction "A1_A1") (pintype "bidirectional"))
    )
    (net (code "60") (name "OUTB1") (class "Default")
      (node (ref "IC1") (pin "15") (pinfunction "OUTB_15") (pintype "output"))
      (node (ref "IC1") (pin "16") (pinfunction "OUTB_16") (pintype "passive"))
      (node (ref "IC1") (pin "21") (pinfunction "OUTB_21") (pintype "passive"))
      (node (ref "IC1") (pin "OUTB") (pinfunction "OUTB_OUTB") (pintype "passive"))
      (node (ref "IC1") (pin "OUTB@1") (pinfunction "OUTB_OUTB@1") (pintype "passive"))
      (node (ref "U$3") (pin "A2") (pinfunction "A2_A2") (pintype "bidirectional"))
    )
    (net (code "61") (name "OUTB2") (class "Default")
      (node (ref "IC2") (pin "15") (pinfunction "OUTB_15") (pintype "output"))
      (node (ref "IC2") (pin "16") (pinfunction "OUTB_16") (pintype "passive"))
      (node (ref "IC2") (pin "21") (pinfunction "OUTB_21") (pintype "passive"))
      (node (ref "IC2") (pin "OUTB") (pinfunction "OUTB_OUTB") (pintype "passive"))
      (node (ref "IC2") (pin "OUTB@1") (pinfunction "OUTB_OUTB@1") (pintype "passive"))
      (node (ref "U$4") (pin "A2") (pinfunction "A2_A2") (pintype "bidirectional"))
    )
    (net (code "62") (name "PWM1") (class "Default")
      (node (ref "IC3") (pin "5") (pinfunction "VIC_5") (pintype "input"))
      (node (ref "PCB1") (pin "40") (pinfunction "GPIO21_40") (pintype "bidirectional"))
    )
    (net (code "63") (name "PWM1EXT") (class "Default")
      (node (ref "IC1") (pin "8") (pinfunction "PWM_8") (pintype "input"))
      (node (ref "IC3") (pin "12") (pinfunction "VOC_12") (pintype "output"))
    )
    (net (code "64") (name "PWM2") (class "Default")
      (node (ref "IC6") (pin "5") (pinfunction "VIC_5") (pintype "input"))
      (node (ref "PCB1") (pin "18") (pinfunction "GEN5/GPIO24_18") (pintype "bidirectional"))
    )
    (net (code "65") (name "PWM2EXT") (class "Default")
      (node (ref "IC2") (pin "8") (pinfunction "PWM_8") (pintype "input"))
      (node (ref "IC6") (pin "12") (pinfunction "VOC_12") (pintype "output"))
    )
    (net (code "66") (name "RTSOUT") (class "Default")
      (node (ref "IC5") (pin "7") (pinfunction "T2OUT_7") (pintype "output"))
      (node (ref "X1") (pin "7") (pinfunction "7_7") (pintype "passive"))
    )
    (net (code "67") (name "RX") (class "Default")
      (node (ref "IC5") (pin "12") (pinfunction "R1OUT_12") (pintype "output"))
      (node (ref "PCB1") (pin "10") (pinfunction "RXD0/GPIO15_10") (pintype "bidirectional"))
    )
    (net (code "68") (name "RXIN") (class "Default")
      (node (ref "IC5") (pin "13") (pinfunction "R1IN_13") (pintype "input"))
      (node (ref "X1") (pin "2") (pinfunction "2_2") (pintype "passive"))
    )
    (net (code "69") (name "SCL") (class "Default")
      (node (ref "IC4") (pin "3") (pinfunction "SCL1_3") (pintype "bidirectional"))
      (node (ref "IC8") (pin "3") (pinfunction "SCL1_3") (pintype "bidirectional"))
      (node (ref "PCB1") (pin "5") (pinfunction "GPIO03/SCL1_5") (pintype "bidirectional"))
      (node (ref "U$11") (pin "A3") (pinfunction "3_A3") (pintype "bidirectional"))
      (node (ref "U$11") (pin "B3") (pinfunction "3_B3") (pintype "bidirectional"))
    )
    (net (code "70") (name "SCLK") (class "Default")
      (node (ref "PCB1") (pin "23") (pinfunction "GPIO11/SCLK_23") (pintype "bidirectional"))
      (node (ref "U$12") (pin "A3") (pinfunction "3_A3") (pintype "bidirectional"))
      (node (ref "U$12") (pin "B3") (pinfunction "3_B3") (pintype "bidirectional"))
    )
    (net (code "71") (name "SDA") (class "Default")
      (node (ref "IC4") (pin "2") (pinfunction "SDA1_2") (pintype "bidirectional"))
      (node (ref "IC8") (pin "2") (pinfunction "SDA1_2") (pintype "bidirectional"))
      (node (ref "PCB1") (pin "3") (pinfunction "GPIO02/SDA1_3") (pintype "bidirectional"))
      (node (ref "U$11") (pin "A5") (pinfunction "5_A5") (pintype "bidirectional"))
      (node (ref "U$11") (pin "B5") (pinfunction "5_B5") (pintype "bidirectional"))
    )
    (net (code "72") (name "TX") (class "Default")
      (node (ref "IC5") (pin "11") (pinfunction "T1IN_11") (pintype "input"))
      (node (ref "PCB1") (pin "8") (pinfunction "TXD0/GPIO14_8") (pintype "bidirectional"))
    )
    (net (code "73") (name "TXOUT") (class "Default")
      (node (ref "IC5") (pin "14") (pinfunction "T1OUT_14") (pintype "output"))
      (node (ref "X1") (pin "3") (pinfunction "3_3") (pintype "passive"))
    )
    (net (code "74") (name "VCCEXT1") (class "Default")
      (node (ref "IC1") (pin "13") (pinfunction "VCC_13") (pintype "power_in"))
      (node (ref "IC1") (pin "23") (pinfunction "VCC_23") (pintype "power_in"))
      (node (ref "IC1") (pin "3") (pinfunction "VCC_3") (pintype "power_in"))
      (node (ref "IC1") (pin "VCC") (pinfunction "VCC_VCC") (pintype "power_in"))
      (node (ref "IC1") (pin "VCC@1") (pinfunction "VCC_VCC@1") (pintype "power_in"))
      (node (ref "U$5") (pin "A1") (pinfunction "A1_A1") (pintype "bidirectional"))
    )
    (net (code "75") (name "VCCEXT2") (class "Default")
      (node (ref "IC2") (pin "13") (pinfunction "VCC_13") (pintype "power_in"))
      (node (ref "IC2") (pin "23") (pinfunction "VCC_23") (pintype "power_in"))
      (node (ref "IC2") (pin "3") (pinfunction "VCC_3") (pintype "power_in"))
      (node (ref "IC2") (pin "VCC") (pinfunction "VCC_VCC") (pintype "power_in"))
      (node (ref "IC2") (pin "VCC@1") (pinfunction "VCC_VCC@1") (pintype "power_in"))
      (node (ref "U$6") (pin "A1") (pinfunction "A1_A1") (pintype "bidirectional"))
    )
    (net (code "76") (name "VCCINT") (class "Default")
      (node (ref "C1") (pin "1") (pinfunction "1_1") (pintype "passive"))
      (node (ref "C14") (pin "1") (pinfunction "1_1") (pintype "passive"))
      (node (ref "C15") (pin "1") (pinfunction "1_1") (pintype "passive"))
      (node (ref "C17") (pin "1") (pinfunction "1_1") (pintype "passive"))
      (node (ref "C2") (pin "1") (pinfunction "1_1") (pintype "passive"))
      (node (ref "C3") (pin "1") (pinfunction "1_1") (pintype "passive"))
      (node (ref "C4") (pin "1") (pinfunction "1_1") (pintype "passive"))
      (node (ref "C9") (pin "1") (pinfunction "1_1") (pintype "passive"))
      (node (ref "IC3") (pin "1") (pinfunction "VDD1_1") (pintype "power_in"))
      (node (ref "IC4") (pin "1") (pinfunction "VDD1_1") (pintype "power_in"))
      (node (ref "IC5") (pin "16") (pinfunction "VCC_16") (pintype "power_in"))
      (node (ref "IC6") (pin "1") (pinfunction "VDD1_1") (pintype "power_in"))
      (node (ref "IC7") (pin "4") (pinfunction "VCC_4") (pintype "power_in"))
      (node (ref "IC8") (pin "1") (pinfunction "VDD1_1") (pintype "power_in"))
      (node (ref "PCB1") (pin "1") (pinfunction "3V3_1") (pintype "power_in"))
      (node (ref "PCB1") (pin "17") (pinfunction "3V3_17") (pintype "power_in"))
      (node (ref "R5") (pin "2") (pinfunction "2_2") (pintype "passive"))
      (node (ref "R6") (pin "2") (pinfunction "2_2") (pintype "passive"))
      (node (ref "R7") (pin "1") (pinfunction "1_1") (pintype "passive"))
      (node (ref "R8") (pin "2") (pinfunction "2_2") (pintype "passive"))
      (node (ref "R9") (pin "2") (pinfunction "2_2") (pintype "passive"))
      (node (ref "U$1") (pin "1") (pinfunction "VDD1_1") (pintype "power_in"))
      (node (ref "U$1") (pin "7") (pinfunction "VE1_7") (pintype "passive"))
      (node (ref "U$11") (pin "A6") (pinfunction "6_A6") (pintype "bidirectional"))
      (node (ref "U$11") (pin "A9") (pinfunction "9_A9") (pintype "bidirectional"))
      (node (ref "U$11") (pin "B6") (pinfunction "6_B6") (pintype "bidirectional"))
      (node (ref "U$11") (pin "B9") (pinfunction "9_B9") (pintype "bidirectional"))
      (node (ref "U$12") (pin "A9") (pinfunction "9_A9") (pintype "bidirectional"))
      (node (ref "U$12") (pin "B9") (pinfunction "9_B9") (pintype "bidirectional"))
      (node (ref "U$2") (pin "1") (pinfunction "VDD1_1") (pintype "power_in"))
      (node (ref "U$2") (pin "7") (pinfunction "VE1_7") (pintype "passive"))
    )
    (net (code "77") (name "unconnected-(PCB1-GPIO04{slash}GCKL-Pad7)") (class "Default")
      (node (ref "PCB1") (pin "7") (pinfunction "GPIO04/GCKL_7") (pintype "bidirectional"))
    )
    (net (code "78") (name "unconnected-(U$11A-7-PadA7)") (class "Default")
      (node (ref "U$11") (pin "A7") (pinfunction "7_A7") (pintype "bidirectional"))
    )
    (net (code "79") (name "unconnected-(U$11A-8-PadA8)") (class "Default")
      (node (ref "U$11") (pin "A8") (pinfunction "8_A8") (pintype "bidirectional"))
    )
    (net (code "80") (name "unconnected-(U$11B-7-PadB7)") (class "Default")
      (node (ref "U$11") (pin "B7") (pinfunction "7_B7") (pintype "bidirectional"))
    )
    (net (code "81") (name "unconnected-(U$11B-8-PadB8)") (class "Default")
      (node (ref "U$11") (pin "B8") (pinfunction "8_B8") (pintype "bidirectional"))
    )
    (net (code "82") (name "unconnected-(U$12A-8-PadA8)") (class "Default")
      (node (ref "U$12") (pin "A8") (pinfunction "8_A8") (pintype "bidirectional"))
    )
    (net (code "83") (name "unconnected-(U$12B-8-PadB8)") (class "Default")
      (node (ref "U$12") (pin "B8") (pinfunction "8_B8") (pintype "bidirectional"))
    )
    (net (code "84") (name "unconnected-(U$14-PCTLZ-Pad6)") (class "Default")
      (node (ref "U$14") (pin "6") (pinfunction "PCTLZ_6") (pintype "bidirectional"))
    )
    (net (code "85") (name "unconnected-(U$15-PCTLZ-Pad6)") (class "Default")
      (node (ref "U$15") (pin "6") (pinfunction "PCTLZ_6") (pintype "bidirectional"))
    )
    (net (code "86") (name "unconnected-(X1-Pad1)") (class "Default")
      (node (ref "X1") (pin "1") (pinfunction "1_1") (pintype "passive"))
    )
    (net (code "87") (name "unconnected-(X1-Pad4)") (class "Default")
      (node (ref "X1") (pin "4") (pinfunction "4_4") (pintype "passive"))
    )
    (net (code "88") (name "unconnected-(X1-Pad6)") (class "Default")
      (node (ref "X1") (pin "6") (pinfunction "6_6") (pintype "passive"))
    )
    (net (code "89") (name "unconnected-(X1-Pad9)") (class "Default")
      (node (ref "X1") (pin "9") (pinfunction "9_9") (pintype "passive"))
    )
  )
)
